# stereo_link.net
KiCad netlist of a schematic drawn in EAGLE
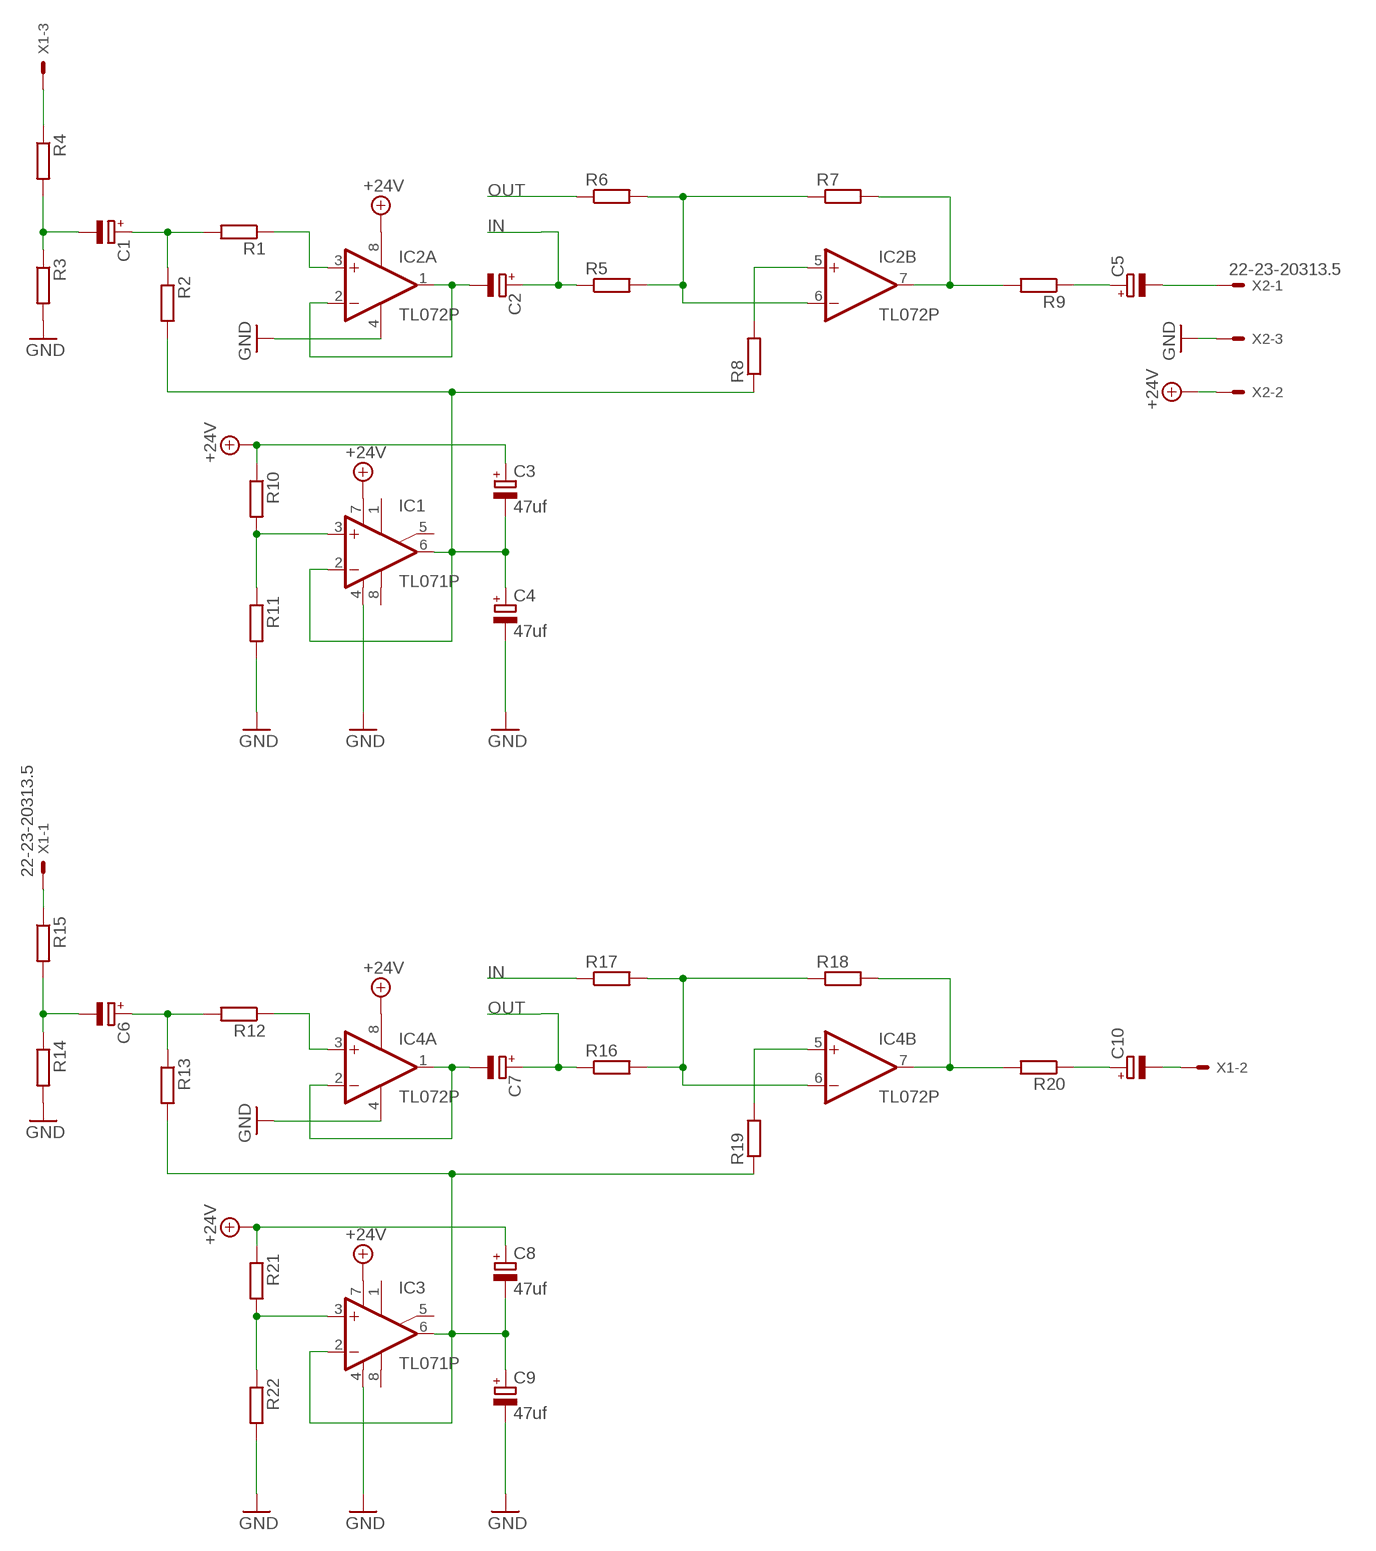
[diagram p0: schematic, sheet 1]

(export (version "E")
  (design (tool "Eeschema 10.0.6"))
  (components
    (comp (ref "C1")
      (value "CPOL-EUE1.8-4")
      (footprint "eagle-import:E1,8-4")
      (libsource (lib "eagle-import") (part "CPOL-EUE1.8-4"))
    )
    (comp (ref "C2")
      (value "CPOL-EUE1.8-4")
      (footprint "eagle-import:E1,8-4")
      (libsource (lib "eagle-import") (part "CPOL-EUE1.8-4"))
    )
    (comp (ref "C3")
      (value "47uf")
      (footprint "eagle-import:E2,5-6E")
      (libsource (lib "eagle-import") (part "CPOL-EUE2,5-6E"))
    )
    (comp (ref "C4")
      (value "47uf")
      (footprint "eagle-import:E2,5-6E")
      (libsource (lib "eagle-import") (part "CPOL-EUE2,5-6E"))
    )
    (comp (ref "C5")
      (value "CPOL-EUE1.8-4")
      (footprint "eagle-import:E1,8-4")
      (libsource (lib "eagle-import") (part "CPOL-EUE1.8-4"))
    )
    (comp (ref "C6")
      (value "CPOL-EUE1.8-4")
      (footprint "eagle-import:E1,8-4")
      (libsource (lib "eagle-import") (part "CPOL-EUE1.8-4"))
    )
    (comp (ref "C7")
      (value "CPOL-EUE1.8-4")
      (footprint "eagle-import:E1,8-4")
      (libsource (lib "eagle-import") (part "CPOL-EUE1.8-4"))
    )
    (comp (ref "C8")
      (value "47uf")
      (footprint "eagle-import:E2,5-6E")
      (libsource (lib "eagle-import") (part "CPOL-EUE2,5-6E"))
    )
    (comp (ref "C9")
      (value "47uf")
      (footprint "eagle-import:E2,5-6E")
      (libsource (lib "eagle-import") (part "CPOL-EUE2,5-6E"))
    )
    (comp (ref "C10")
      (value "CPOL-EUE1.8-4")
      (footprint "eagle-import:E1,8-4")
      (libsource (lib "eagle-import") (part "CPOL-EUE1.8-4"))
    )
    (comp (ref "IC1")
      (value "TL071P")
      (footprint "eagle-import:DIL08")
      (libsource (lib "eagle-import") (part "TL071P"))
    )
    (comp (ref "IC2")
      (value "TL072P")
      (footprint "eagle-import:DIL08")
      (libsource (lib "eagle-import") (part "TL072P"))
    )
    (comp (ref "IC3")
      (value "TL071P")
      (footprint "eagle-import:DIL08")
      (libsource (lib "eagle-import") (part "TL071P"))
    )
    (comp (ref "IC4")
      (value "TL072P")
      (footprint "eagle-import:DIL08")
      (libsource (lib "eagle-import") (part "TL072P"))
    )
    (comp (ref "R1")
      (value "R-EU_0204/7")
      (footprint "eagle-import:0204_7")
      (libsource (lib "eagle-import") (part "R-EU_0204/7"))
    )
    (comp (ref "R2")
      (value "R-EU_0204/7")
      (footprint "eagle-import:0204_7")
      (libsource (lib "eagle-import") (part "R-EU_0204/7"))
    )
    (comp (ref "R3")
      (value "R-EU_0204/7")
      (footprint "eagle-import:0204_7")
      (libsource (lib "eagle-import") (part "R-EU_0204/7"))
    )
    (comp (ref "R4")
      (value "R-EU_0204/7")
      (footprint "eagle-import:0204_7")
      (libsource (lib "eagle-import") (part "R-EU_0204/7"))
    )
    (comp (ref "R5")
      (value "R-EU_0204/7")
      (footprint "eagle-import:0204_7")
      (libsource (lib "eagle-import") (part "R-EU_0204/7"))
    )
    (comp (ref "R6")
      (value "R-EU_0204/7")
      (footprint "eagle-import:0204_7")
      (libsource (lib "eagle-import") (part "R-EU_0204/7"))
    )
    (comp (ref "R7")
      (value "R-EU_0204/7")
      (footprint "eagle-import:0204_7")
      (libsource (lib "eagle-import") (part "R-EU_0204/7"))
    )
    (comp (ref "R8")
      (value "R-EU_0204/7")
      (footprint "eagle-import:0204_7")
      (libsource (lib "eagle-import") (part "R-EU_0204/7"))
    )
    (comp (ref "R9")
      (value "R-EU_0204/7")
      (footprint "eagle-import:0204_7")
      (libsource (lib "eagle-import") (part "R-EU_0204/7"))
    )
    (comp (ref "R10")
      (value "R-EU_0204/7")
      (footprint "eagle-import:0204_7")
      (libsource (lib "eagle-import") (part "R-EU_0204/7"))
    )
    (comp (ref "R11")
      (value "R-EU_0204/7")
      (footprint "eagle-import:0204_7")
      (libsource (lib "eagle-import") (part "R-EU_0204/7"))
    )
    (comp (ref "R12")
      (value "R-EU_0204/7")
      (footprint "eagle-import:0204_7")
      (libsource (lib "eagle-import") (part "R-EU_0204/7"))
    )
    (comp (ref "R13")
      (value "R-EU_0204/7")
      (footprint "eagle-import:0204_7")
      (libsource (lib "eagle-import") (part "R-EU_0204/7"))
    )
    (comp (ref "R14")
      (value "R-EU_0204/7")
      (footprint "eagle-import:0204_7")
      (libsource (lib "eagle-import") (part "R-EU_0204/7"))
    )
    (comp (ref "R15")
      (value "R-EU_0204/7")
      (footprint "eagle-import:0204_7")
      (libsource (lib "eagle-import") (part "R-EU_0204/7"))
    )
    (comp (ref "R16")
      (value "R-EU_0204/7")
      (footprint "eagle-import:0204_7")
      (libsource (lib "eagle-import") (part "R-EU_0204/7"))
    )
    (comp (ref "R17")
      (value "R-EU_0204/7")
      (footprint "eagle-import:0204_7")
      (libsource (lib "eagle-import") (part "R-EU_0204/7"))
    )
    (comp (ref "R18")
      (value "R-EU_0204/7")
      (footprint "eagle-import:0204_7")
      (libsource (lib "eagle-import") (part "R-EU_0204/7"))
    )
    (comp (ref "R19")
      (value "R-EU_0204/7")
      (footprint "eagle-import:0204_7")
      (libsource (lib "eagle-import") (part "R-EU_0204/7"))
    )
    (comp (ref "R20")
      (value "R-EU_0204/7")
      (footprint "eagle-import:0204_7")
      (libsource (lib "eagle-import") (part "R-EU_0204/7"))
    )
    (comp (ref "R21")
      (value "R-EU_0204/7")
      (footprint "eagle-import:0204_7")
      (libsource (lib "eagle-import") (part "R-EU_0204/7"))
    )
    (comp (ref "R22")
      (value "R-EU_0204/7")
      (footprint "eagle-import:0204_7")
      (libsource (lib "eagle-import") (part "R-EU_0204/7"))
    )
    (comp (ref "X1")
      (value "22-23-20313.5")
      (footprint "eagle-import:3.5MM")
      (libsource (lib "eagle-import") (part "22-23-20313.5"))
    )
    (comp (ref "X2")
      (value "22-23-20313.5")
      (footprint "eagle-import:3.5MM")
      (libsource (lib "eagle-import") (part "22-23-20313.5"))
    )
  )
  (nets
    (net (code "1") (name "+24V") (class "Default")
      (node (ref "C3") (pin "+") (pinfunction "+_+") (pintype "passive"))
      (node (ref "C8") (pin "+") (pinfunction "+_+") (pintype "passive"))
      (node (ref "IC1") (pin "7") (pinfunction "V+_7") (pintype "power_in"))
      (node (ref "IC2") (pin "8") (pinfunction "V+_8") (pintype "power_in"))
      (node (ref "IC3") (pin "7") (pinfunction "V+_7") (pintype "power_in"))
      (node (ref "IC4") (pin "8") (pinfunction "V+_8") (pintype "power_in"))
      (node (ref "R10") (pin "1") (pinfunction "1_1") (pintype "passive"))
      (node (ref "R21") (pin "1") (pinfunction "1_1") (pintype "passive"))
      (node (ref "X2") (pin "P$2") (pinfunction "S_P$2") (pintype "passive"))
    )
    (net (code "2") (name "/IN") (class "Default")
      (node (ref "C2") (pin "+") (pinfunction "+_+") (pintype "passive"))
      (node (ref "R17") (pin "1") (pinfunction "1_1") (pintype "passive"))
      (node (ref "R5") (pin "1") (pinfunction "1_1") (pintype "passive"))
    )
    (net (code "3") (name "/OUT") (class "Default")
      (node (ref "C7") (pin "+") (pinfunction "+_+") (pintype "passive"))
      (node (ref "R16") (pin "1") (pinfunction "1_1") (pintype "passive"))
      (node (ref "R6") (pin "1") (pinfunction "1_1") (pintype "passive"))
    )
    (net (code "4") (name "GND") (class "Default")
      (node (ref "C4") (pin "-") (pinfunction "-_-") (pintype "passive"))
      (node (ref "C9") (pin "-") (pinfunction "-_-") (pintype "passive"))
      (node (ref "IC1") (pin "4") (pinfunction "V-_4") (pintype "power_in"))
      (node (ref "IC2") (pin "4") (pinfunction "V-_4") (pintype "power_in"))
      (node (ref "IC3") (pin "4") (pinfunction "V-_4") (pintype "power_in"))
      (node (ref "IC4") (pin "4") (pinfunction "V-_4") (pintype "power_in"))
      (node (ref "R11") (pin "2") (pinfunction "2_2") (pintype "passive"))
      (node (ref "R14") (pin "2") (pinfunction "2_2") (pintype "passive"))
      (node (ref "R22") (pin "2") (pinfunction "2_2") (pintype "passive"))
      (node (ref "R3") (pin "2") (pinfunction "2_2") (pintype "passive"))
      (node (ref "X2") (pin "P$3") (pinfunction "S_P$3") (pintype "passive"))
    )
    (net (code "5") (name "Net-(C1-Pad+)") (class "Default")
      (node (ref "C1") (pin "+") (pinfunction "+_+") (pintype "passive"))
      (node (ref "R1") (pin "2") (pinfunction "2_2") (pintype "passive"))
      (node (ref "R2") (pin "1") (pinfunction "1_1") (pintype "passive"))
    )
    (net (code "6") (name "Net-(C1-Pad-)") (class "Default")
      (node (ref "C1") (pin "-") (pinfunction "-_-") (pintype "passive"))
      (node (ref "R3") (pin "1") (pinfunction "1_1") (pintype "passive"))
      (node (ref "R4") (pin "2") (pinfunction "2_2") (pintype "passive"))
    )
    (net (code "7") (name "Net-(C5-Pad+)") (class "Default")
      (node (ref "C5") (pin "+") (pinfunction "+_+") (pintype "passive"))
      (node (ref "R9") (pin "1") (pinfunction "1_1") (pintype "passive"))
    )
    (net (code "8") (name "Net-(C6-Pad+)") (class "Default")
      (node (ref "C6") (pin "+") (pinfunction "+_+") (pintype "passive"))
      (node (ref "R12") (pin "2") (pinfunction "2_2") (pintype "passive"))
      (node (ref "R13") (pin "1") (pinfunction "1_1") (pintype "passive"))
    )
    (net (code "9") (name "Net-(C6-Pad-)") (class "Default")
      (node (ref "C6") (pin "-") (pinfunction "-_-") (pintype "passive"))
      (node (ref "R14") (pin "1") (pinfunction "1_1") (pintype "passive"))
      (node (ref "R15") (pin "2") (pinfunction "2_2") (pintype "passive"))
    )
    (net (code "10") (name "Net-(C10-Pad+)") (class "Default")
      (node (ref "C10") (pin "+") (pinfunction "+_+") (pintype "passive"))
      (node (ref "R20") (pin "1") (pinfunction "1_1") (pintype "passive"))
    )
    (net (code "11") (name "Net-(IC1-+IN)") (class "Default")
      (node (ref "IC1") (pin "3") (pinfunction "+IN_3") (pintype "input"))
      (node (ref "R10") (pin "2") (pinfunction "2_2") (pintype "passive"))
      (node (ref "R11") (pin "1") (pinfunction "1_1") (pintype "passive"))
    )
    (net (code "12") (name "Net-(IC1--IN)") (class "Default")
      (node (ref "C3") (pin "-") (pinfunction "-_-") (pintype "passive"))
      (node (ref "C4") (pin "+") (pinfunction "+_+") (pintype "passive"))
      (node (ref "IC1") (pin "2") (pinfunction "-IN_2") (pintype "input"))
      (node (ref "IC1") (pin "6") (pinfunction "OUT_6") (pintype "output"))
      (node (ref "R2") (pin "2") (pinfunction "2_2") (pintype "passive"))
      (node (ref "R8") (pin "1") (pinfunction "1_1") (pintype "passive"))
    )
    (net (code "13") (name "Net-(IC2A-+IN)") (class "Default")
      (node (ref "IC2") (pin "3") (pinfunction "+IN_3") (pintype "input"))
      (node (ref "R1") (pin "1") (pinfunction "1_1") (pintype "passive"))
    )
    (net (code "14") (name "Net-(IC2A--IN)") (class "Default")
      (node (ref "C2") (pin "-") (pinfunction "-_-") (pintype "passive"))
      (node (ref "IC2") (pin "1") (pinfunction "OUT_1") (pintype "output"))
      (node (ref "IC2") (pin "2") (pinfunction "-IN_2") (pintype "input"))
    )
    (net (code "15") (name "Net-(IC2B-+IN)") (class "Default")
      (node (ref "IC2") (pin "5") (pinfunction "+IN_5") (pintype "input"))
      (node (ref "R8") (pin "2") (pinfunction "2_2") (pintype "passive"))
    )
    (net (code "16") (name "Net-(IC2B--IN)") (class "Default")
      (node (ref "IC2") (pin "6") (pinfunction "-IN_6") (pintype "input"))
      (node (ref "R5") (pin "2") (pinfunction "2_2") (pintype "passive"))
      (node (ref "R6") (pin "2") (pinfunction "2_2") (pintype "passive"))
      (node (ref "R7") (pin "1") (pinfunction "1_1") (pintype "passive"))
    )
    (net (code "17") (name "Net-(IC2B-OUT)") (class "Default")
      (node (ref "IC2") (pin "7") (pinfunction "OUT_7") (pintype "output"))
      (node (ref "R7") (pin "2") (pinfunction "2_2") (pintype "passive"))
      (node (ref "R9") (pin "2") (pinfunction "2_2") (pintype "passive"))
    )
    (net (code "18") (name "Net-(IC3-+IN)") (class "Default")
      (node (ref "IC3") (pin "3") (pinfunction "+IN_3") (pintype "input"))
      (node (ref "R21") (pin "2") (pinfunction "2_2") (pintype "passive"))
      (node (ref "R22") (pin "1") (pinfunction "1_1") (pintype "passive"))
    )
    (net (code "19") (name "Net-(IC3--IN)") (class "Default")
      (node (ref "C8") (pin "-") (pinfunction "-_-") (pintype "passive"))
      (node (ref "C9") (pin "+") (pinfunction "+_+") (pintype "passive"))
      (node (ref "IC3") (pin "2") (pinfunction "-IN_2") (pintype "input"))
      (node (ref "IC3") (pin "6") (pinfunction "OUT_6") (pintype "output"))
      (node (ref "R13") (pin "2") (pinfunction "2_2") (pintype "passive"))
      (node (ref "R19") (pin "1") (pinfunction "1_1") (pintype "passive"))
    )
    (net (code "20") (name "Net-(IC4A-+IN)") (class "Default")
      (node (ref "IC4") (pin "3") (pinfunction "+IN_3") (pintype "input"))
      (node (ref "R12") (pin "1") (pinfunction "1_1") (pintype "passive"))
    )
    (net (code "21") (name "Net-(IC4A--IN)") (class "Default")
      (node (ref "C7") (pin "-") (pinfunction "-_-") (pintype "passive"))
      (node (ref "IC4") (pin "1") (pinfunction "OUT_1") (pintype "output"))
      (node (ref "IC4") (pin "2") (pinfunction "-IN_2") (pintype "input"))
    )
    (net (code "22") (name "Net-(IC4B-+IN)") (class "Default")
      (node (ref "IC4") (pin "5") (pinfunction "+IN_5") (pintype "input"))
      (node (ref "R19") (pin "2") (pinfunction "2_2") (pintype "passive"))
    )
    (net (code "23") (name "Net-(IC4B--IN)") (class "Default")
      (node (ref "IC4") (pin "6") (pinfunction "-IN_6") (pintype "input"))
      (node (ref "R16") (pin "2") (pinfunction "2_2") (pintype "passive"))
      (node (ref "R17") (pin "2") (pinfunction "2_2") (pintype "passive"))
      (node (ref "R18") (pin "1") (pinfunction "1_1") (pintype "passive"))
    )
    (net (code "24") (name "Net-(IC4B-OUT)") (class "Default")
      (node (ref "IC4") (pin "7") (pinfunction "OUT_7") (pintype "output"))
      (node (ref "R18") (pin "2") (pinfunction "2_2") (pintype "passive"))
      (node (ref "R20") (pin "2") (pinfunction "2_2") (pintype "passive"))
    )
    (net (code "25") (name "Net-(X1A-S)") (class "Default")
      (node (ref "R15") (pin "1") (pinfunction "1_1") (pintype "passive"))
      (node (ref "X1") (pin "P$1") (pinfunction "S_P$1") (pintype "passive"))
    )
    (net (code "26") (name "Net-(X1B-S)") (class "Default")
      (node (ref "C10") (pin "-") (pinfunction "-_-") (pintype "passive"))
      (node (ref "X1") (pin "P$2") (pinfunction "S_P$2") (pintype "passive"))
    )
    (net (code "27") (name "Net-(X1C-S)") (class "Default")
      (node (ref "R4") (pin "1") (pinfunction "1_1") (pintype "passive"))
      (node (ref "X1") (pin "P$3") (pinfunction "S_P$3") (pintype "passive"))
    )
    (net (code "28") (name "Net-(X2A-S)") (class "Default")
      (node (ref "C5") (pin "-") (pinfunction "-_-") (pintype "passive"))
      (node (ref "X2") (pin "P$1") (pinfunction "S_P$1") (pintype "passive"))
    )
    (net (code "29") (name "unconnected-(IC1-ON1-Pad1)") (class "Default")
      (node (ref "IC1") (pin "1") (pinfunction "ON1_1") (pintype "passive"))
    )
    (net (code "30") (name "unconnected-(IC1-ON2-Pad5)") (class "Default")
      (node (ref "IC1") (pin "5") (pinfunction "ON2_5") (pintype "passive"))
    )
    (net (code "31") (name "unconnected-(IC1-OPT-Pad8)") (class "Default")
      (node (ref "IC1") (pin "8") (pinfunction "OPT_8") (pintype "passive"))
    )
    (net (code "32") (name "unconnected-(IC3-ON1-Pad1)") (class "Default")
      (node (ref "IC3") (pin "1") (pinfunction "ON1_1") (pintype "passive"))
    )
    (net (code "33") (name "unconnected-(IC3-ON2-Pad5)") (class "Default")
      (node (ref "IC3") (pin "5") (pinfunction "ON2_5") (pintype "passive"))
    )
    (net (code "34") (name "unconnected-(IC3-OPT-Pad8)") (class "Default")
      (node (ref "IC3") (pin "8") (pinfunction "OPT_8") (pintype "passive"))
    )
  )
)
